# L298N_Motor.net
KiCad netlist of a schematic drawn in Altium Designer
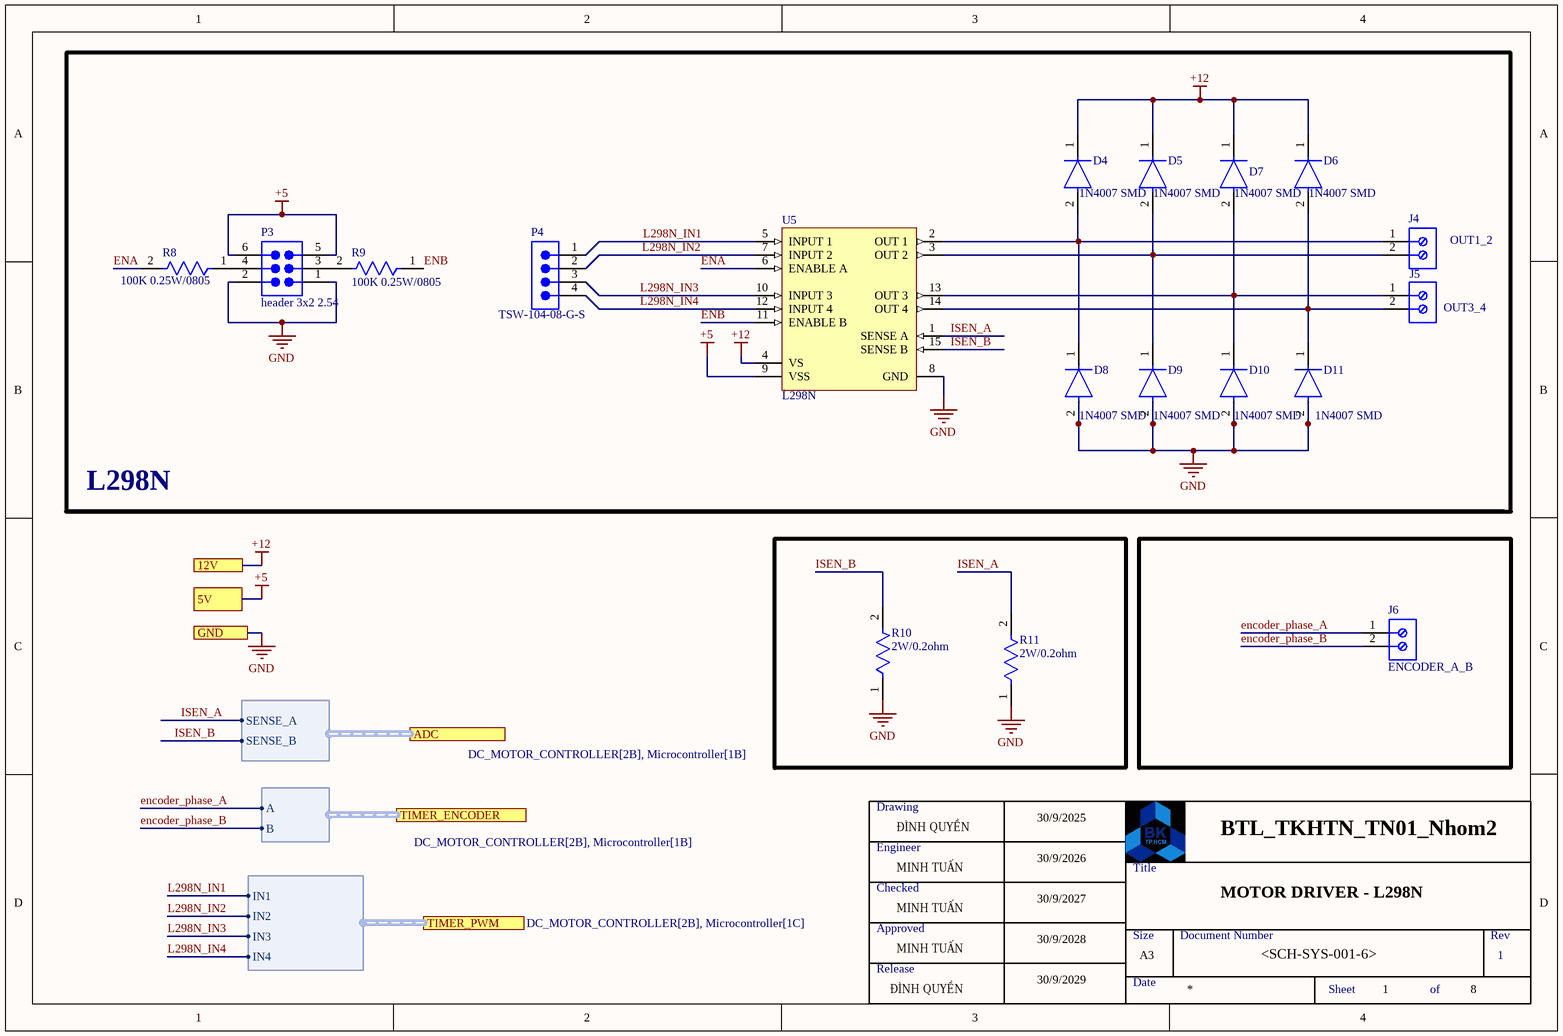
[diagram p0: L298N_Motor.SchDoc]

(export (version "E")
  (design (tool "Eeschema 10.0.6"))
  (components
    (comp (ref "D4")
      (value "1N4007 SMD")
      (footprint "FP-1N4007_SMD-IPC_C")
      (description "Rectifier, 1Kv, 1A, Do-214Ac Rohs Compliant: Yes")
      (libsource (lib "Altium Content Vault") (part "d7152d700b627762746794eb795d46e"))
    )
    (comp (ref "D5")
      (value "1N4007 SMD")
      (footprint "FP-1N4007_SMD-IPC_C")
      (description "Rectifier, 1Kv, 1A, Do-214Ac Rohs Compliant: Yes")
      (libsource (lib "Altium Content Vault") (part "d7152d700b627762746794eb795d46e"))
    )
    (comp (ref "D6")
      (value "1N4007 SMD")
      (footprint "FP-1N4007_SMD-IPC_C")
      (description "Rectifier, 1Kv, 1A, Do-214Ac Rohs Compliant: Yes")
      (libsource (lib "Altium Content Vault") (part "d7152d700b627762746794eb795d46e"))
    )
    (comp (ref "D7")
      (value "1N4007 SMD")
      (footprint "FP-1N4007_SMD-IPC_C")
      (description "Rectifier, 1Kv, 1A, Do-214Ac Rohs Compliant: Yes")
      (libsource (lib "Altium Content Vault") (part "d7152d700b627762746794eb795d46e"))
    )
    (comp (ref "D8")
      (value "1N4007 SMD")
      (footprint "FP-1N4007_SMD-IPC_C")
      (description "Rectifier, 1Kv, 1A, Do-214Ac Rohs Compliant: Yes")
      (libsource (lib "Altium Content Vault") (part "d7152d700b627762746794eb795d46e"))
    )
    (comp (ref "D9")
      (value "1N4007 SMD")
      (footprint "FP-1N4007_SMD-IPC_C")
      (description "Rectifier, 1Kv, 1A, Do-214Ac Rohs Compliant: Yes")
      (libsource (lib "Altium Content Vault") (part "d7152d700b627762746794eb795d46e"))
    )
    (comp (ref "D10")
      (value "1N4007 SMD")
      (footprint "FP-1N4007_SMD-IPC_C")
      (description "Rectifier, 1Kv, 1A, Do-214Ac Rohs Compliant: Yes")
      (libsource (lib "Altium Content Vault") (part "d7152d700b627762746794eb795d46e"))
    )
    (comp (ref "D11")
      (value "1N4007 SMD")
      (footprint "FP-1N4007_SMD-IPC_C")
      (description "Rectifier, 1Kv, 1A, Do-214Ac Rohs Compliant: Yes")
      (libsource (lib "Altium Content Vault") (part "d7152d700b627762746794eb795d46e"))
    )
    (comp (ref "J4")
      (value "OUT1_2")
      (footprint "691254710002")
      (libsource (lib "Altium Content Vault") (part "TBL - 1R - 02P - Screw"))
    )
    (comp (ref "J5")
      (value "OUT3_4")
      (footprint "691254710002")
      (libsource (lib "Altium Content Vault") (part "TBL - 1R - 02P - Screw"))
    )
    (comp (ref "J6")
      (value "ENCODER_A_B")
      (footprint "691254710002")
      (libsource (lib "Altium Content Vault") (part "TBL - 1R - 02P - Screw"))
    )
    (comp (ref "P3")
      (value "header 3x2 2.54")
      (footprint "SMTC-TSW-103-08-X-D")
      (description "0.025\" SQ Post Header, Through-hole, Vertical, -55 to 125 degC, 2.54 mm Pitch, 6-Pin, Male, RoHS")
      (fields (field (name "MANUFACTURER") "Samtec") (field (name "PARTNUMBER") "TSW-103-08-F-D"))
      (libsource (lib "Altium Content Vault") (part "SMTC-TSW-103-08-X-D"))
    )
    (comp (ref "P4")
      (value "TSW-104-08-G-S")
      (footprint "SMTC-TSW-104-08-X-S")
      (description "0.025\" SQ Post Header, Through-hole, Vertical, -55 to 125 degC, 2.54 mm Pitch, 4-Pin, Male, RoHS")
      (fields (field (name "MANUFACTURER") "Samtec"))
      (libsource (lib "Altium Content Vault") (part "SMTC-TSW-104-08-X-S"))
    )
    (comp (ref "R8")
      (value "100K 0.25W/0805")
      (footprint "FP-AF0805-IPC_C")
      (description "Anti-Sulfurated Chip Resistor Automotive Grade 75Ω 1% 0.125W ±100ppm/°C 0805")
      (fields (field (name "TOLERANCE") "1%"))
      (libsource (lib "Altium Content Vault") (part "1029c3af85768c4190bb7ad29bc67b5"))
    )
    (comp (ref "R9")
      (value "100K 0.25W/0805")
      (footprint "FP-AF0805-IPC_C")
      (description "Anti-Sulfurated Chip Resistor Automotive Grade 75Ω 1% 0.125W ±100ppm/°C 0805")
      (fields (field (name "TOLERANCE") "1%"))
      (libsource (lib "Altium Content Vault") (part "1029c3af85768c4190bb7ad29bc67b5"))
    )
    (comp (ref "R10")
      (value "2W/0.2ohm")
      (footprint "FP-ERG3S-MFG")
      (description "ERG-3SJ361A Res Metal Oxide Film 360 Ohm 5% 3W ±300ppm/C Conformal Coated AXL")
      (fields (field (name "TOLERANCE") "5%"))
      (libsource (lib "Altium Content Vault") (part "1029c3af85768c4190bb7ad29bc67b5"))
    )
    (comp (ref "R11")
      (value "2W/0.2ohm")
      (footprint "FP-ERG3S-MFG")
      (description "ERG-3SJ361A Res Metal Oxide Film 360 Ohm 5% 3W ±300ppm/C Conformal Coated AXL")
      (fields (field (name "TOLERANCE") "5%"))
      (libsource (lib "Altium Content Vault") (part "1029c3af85768c4190bb7ad29bc67b5"))
    )
    (comp (ref "U5")
      (value "L298N")
      (footprint "STM-FM-15")
      (description "Dual Full-Bridge Driver, 4.8 to 46 V, -40 to 150 degC, 15-Pin FM (MW 15L), RoHS, Tube")
      (fields (field (name "MANUFACTURER") "STMicroelectronics") (field (name "PARTNUMBER") "L298"))
      (libsource (lib "Altium Content Vault") (part "STM-L298-15"))
    )
  )
  (nets
    (net (code "4") (name "+5") (class "Default")
      (node (ref "P3") (pin "5") (pinfunction "5_5") (pintype "passive"))
      (node (ref "P3") (pin "6") (pinfunction "6_6") (pintype "passive"))
      (node (ref "U5") (pin "9") (pinfunction "VSS_9") (pintype "power_in"))
    )
    (net (code "5") (name "+12") (class "Default")
      (node (ref "D4") (pin "1") (pinfunction "C_1") (pintype "passive"))
      (node (ref "D5") (pin "1") (pinfunction "C_1") (pintype "passive"))
      (node (ref "D6") (pin "1") (pinfunction "C_1") (pintype "passive"))
      (node (ref "D7") (pin "1") (pinfunction "C_1") (pintype "passive"))
      (node (ref "U5") (pin "4") (pinfunction "VS_4") (pintype "power_in"))
    )
    (net (code "6") (name "/ENA") (class "Default")
      (node (ref "R8") (pin "2") (pinfunction "2_2") (pintype "passive"))
      (node (ref "U5") (pin "6") (pinfunction "ENABLE_A_6") (pintype "input"))
    )
    (net (code "7") (name "/ENB") (class "Default")
      (node (ref "R9") (pin "1") (pinfunction "1_1") (pintype "passive"))
      (node (ref "U5") (pin "11") (pinfunction "ENABLE_B_11") (pintype "input"))
    )
    (net (code "8") (name "/ISEN_A") (class "Default")
      (node (ref "R11") (pin "2") (pinfunction "2_2") (pintype "passive"))
      (node (ref "U5") (pin "1") (pinfunction "SENSE_A_1") (pintype "input"))
    )
    (net (code "9") (name "/ISEN_B") (class "Default")
      (node (ref "R10") (pin "2") (pinfunction "2_2") (pintype "passive"))
      (node (ref "U5") (pin "15") (pinfunction "SENSE_B_15") (pintype "input"))
    )
    (net (code "10") (name "/L298N_IN1") (class "Default")
      (node (ref "P4") (pin "1") (pinfunction "1_1") (pintype "passive"))
      (node (ref "U5") (pin "5") (pinfunction "INPUT_1_5") (pintype "input"))
    )
    (net (code "11") (name "/L298N_IN2") (class "Default")
      (node (ref "P4") (pin "2") (pinfunction "2_2") (pintype "passive"))
      (node (ref "U5") (pin "7") (pinfunction "INPUT_2_7") (pintype "input"))
    )
    (net (code "12") (name "/L298N_IN3") (class "Default")
      (node (ref "P4") (pin "3") (pinfunction "3_3") (pintype "passive"))
      (node (ref "U5") (pin "10") (pinfunction "INPUT_3_10") (pintype "input"))
    )
    (net (code "13") (name "/L298N_IN4") (class "Default")
      (node (ref "P4") (pin "4") (pinfunction "4_4") (pintype "passive"))
      (node (ref "U5") (pin "12") (pinfunction "INPUT_4_12") (pintype "input"))
    )
    (net (code "14") (name "/encoder_phase_A") (class "Default")
      (node (ref "J6") (pin "1") (pinfunction "1_1") (pintype "passive"))
    )
    (net (code "15") (name "/encoder_phase_B") (class "Default")
      (node (ref "J6") (pin "2") (pinfunction "2_2") (pintype "passive"))
    )
    (net (code "19") (name "GND") (class "Default")
      (node (ref "D10") (pin "2") (pinfunction "A_2") (pintype "passive"))
      (node (ref "D11") (pin "2") (pinfunction "A_2") (pintype "passive"))
      (node (ref "D8") (pin "2") (pinfunction "A_2") (pintype "passive"))
      (node (ref "D9") (pin "2") (pinfunction "A_2") (pintype "passive"))
      (node (ref "P3") (pin "1") (pinfunction "1_1") (pintype "passive"))
      (node (ref "P3") (pin "2") (pinfunction "2_2") (pintype "passive"))
      (node (ref "R10") (pin "1") (pinfunction "1_1") (pintype "passive"))
      (node (ref "R11") (pin "1") (pinfunction "1_1") (pintype "passive"))
      (node (ref "U5") (pin "8") (pinfunction "GND_8") (pintype "power_in"))
    )
    (net (code "20") (name "Net-(D4-A)") (class "Default")
      (node (ref "D4") (pin "2") (pinfunction "A_2") (pintype "passive"))
      (node (ref "D8") (pin "1") (pinfunction "C_1") (pintype "passive"))
      (node (ref "J4") (pin "1") (pinfunction "1_1") (pintype "passive"))
      (node (ref "U5") (pin "2") (pinfunction "OUT_1_2") (pintype "output"))
    )
    (net (code "21") (name "Net-(D5-A)") (class "Default")
      (node (ref "D5") (pin "2") (pinfunction "A_2") (pintype "passive"))
      (node (ref "D9") (pin "1") (pinfunction "C_1") (pintype "passive"))
      (node (ref "J4") (pin "2") (pinfunction "2_2") (pintype "passive"))
      (node (ref "U5") (pin "3") (pinfunction "OUT_2_3") (pintype "output"))
    )
    (net (code "22") (name "Net-(D10-C)") (class "Default")
      (node (ref "D10") (pin "1") (pinfunction "C_1") (pintype "passive"))
      (node (ref "D7") (pin "2") (pinfunction "A_2") (pintype "passive"))
      (node (ref "J5") (pin "1") (pinfunction "1_1") (pintype "passive"))
      (node (ref "U5") (pin "13") (pinfunction "OUT_3_13") (pintype "output"))
    )
    (net (code "23") (name "Net-(D11-C)") (class "Default")
      (node (ref "D11") (pin "1") (pinfunction "C_1") (pintype "passive"))
      (node (ref "D6") (pin "2") (pinfunction "A_2") (pintype "passive"))
      (node (ref "J5") (pin "2") (pinfunction "2_2") (pintype "passive"))
      (node (ref "U5") (pin "14") (pinfunction "OUT_4_14") (pintype "output"))
    )
    (net (code "24") (name "Net-(P3-Pad3)") (class "Default")
      (node (ref "P3") (pin "3") (pinfunction "3_3") (pintype "passive"))
      (node (ref "R9") (pin "2") (pinfunction "2_2") (pintype "passive"))
    )
    (net (code "25") (name "Net-(P3-Pad4)") (class "Default")
      (node (ref "P3") (pin "4") (pinfunction "4_4") (pintype "passive"))
      (node (ref "R8") (pin "1") (pinfunction "1_1") (pintype "passive"))
    )
  )
)
